# Temp.net
KiCad netlist of a schematic drawn in EAGLE
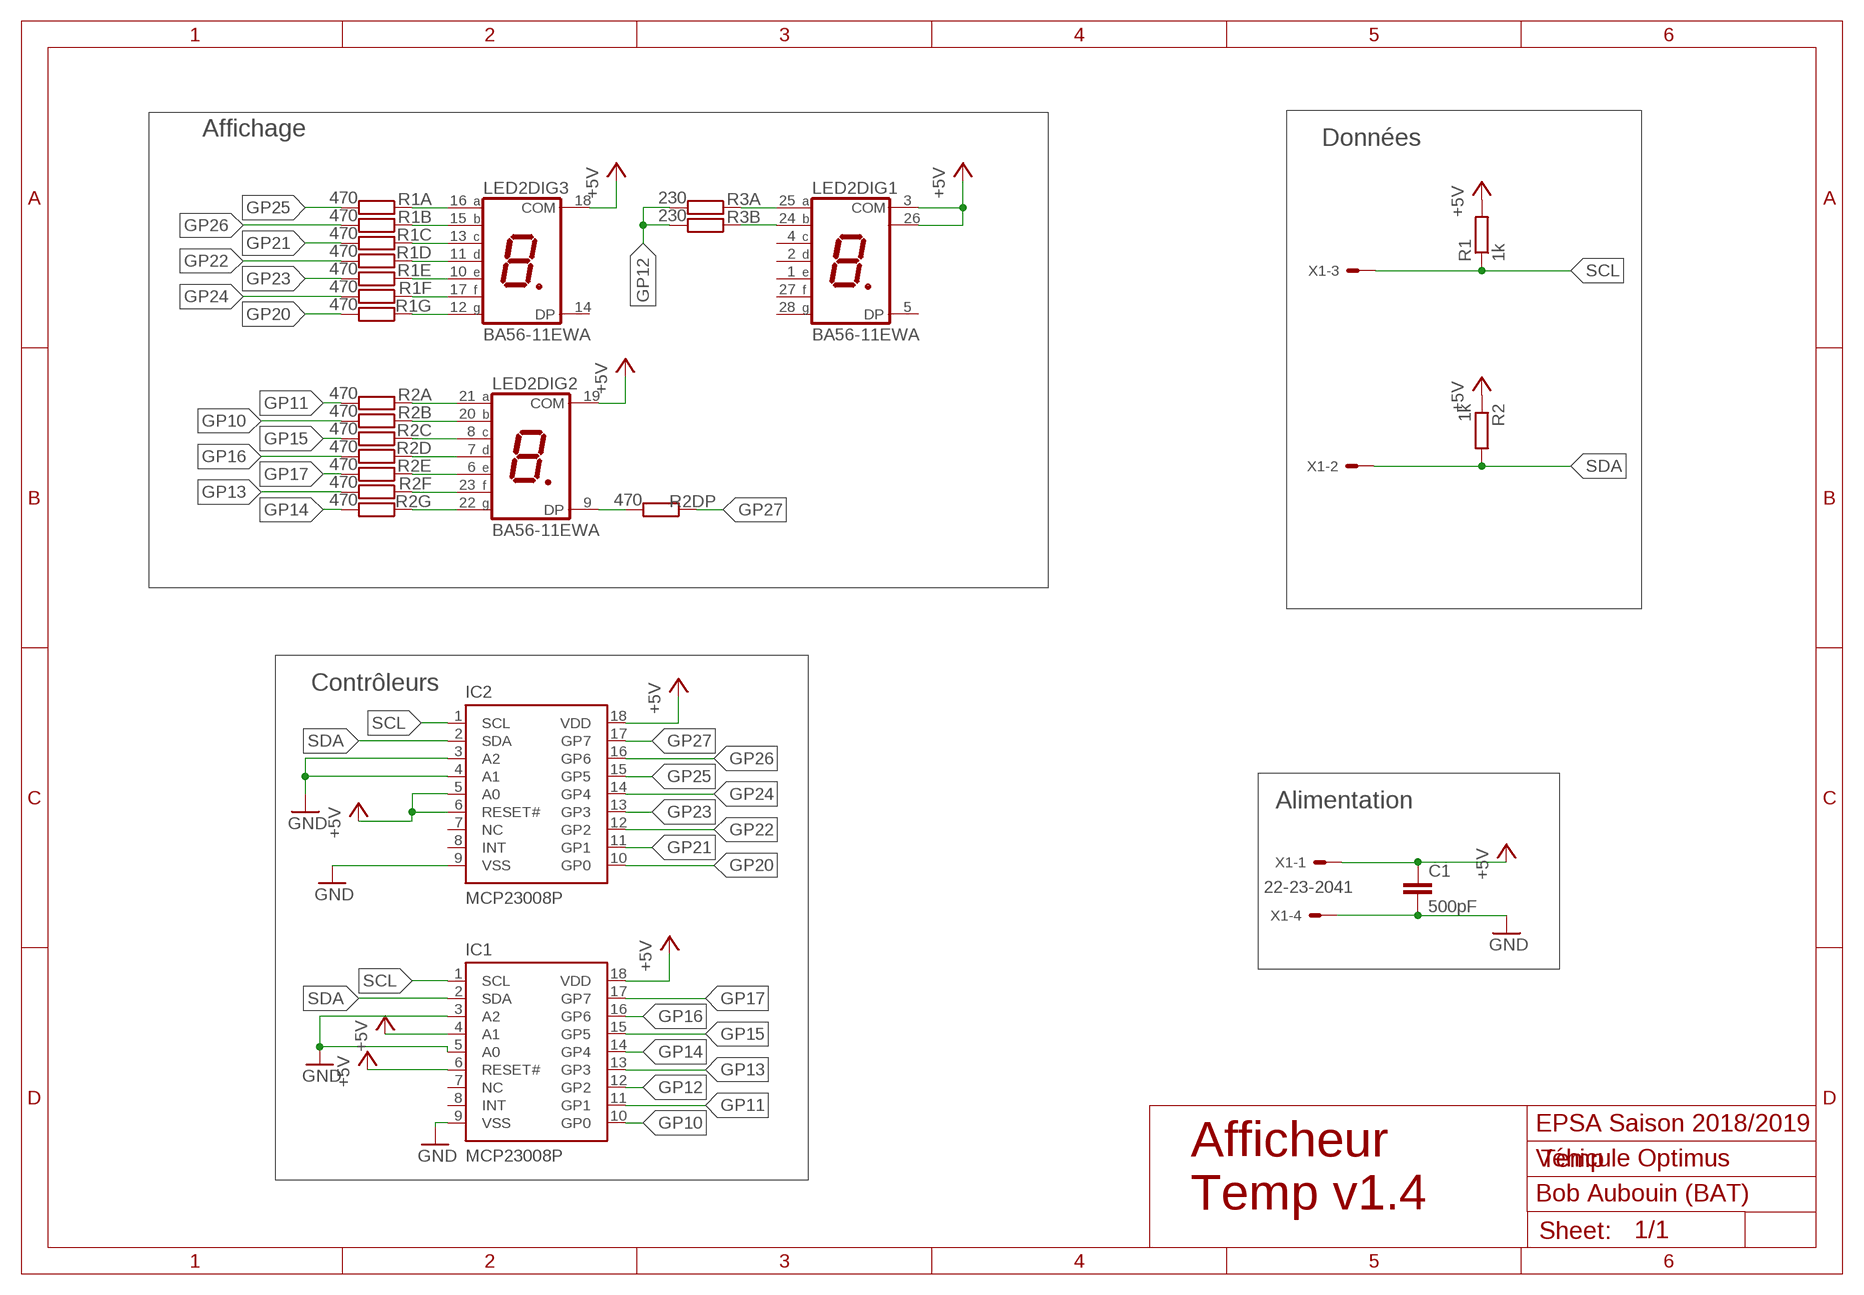
[diagram p0: schematic, sheet 1]

(export (version "E")
  (design (tool "Eeschema 10.0.6"))
  (components
    (comp (ref "C1")
      (value "500pF")
      (footprint "eagle-import:C025-025X050")
      (libsource (lib "eagle-import") (part "C-EU025-025X050"))
    )
    (comp (ref "IC1")
      (value "MCP23008P")
      (footprint "eagle-import:DIL18")
      (libsource (lib "eagle-import") (part "MCP23008P"))
    )
    (comp (ref "IC2")
      (value "MCP23008P")
      (footprint "eagle-import:DIL18")
      (libsource (lib "eagle-import") (part "MCP23008P"))
    )
    (comp (ref "LED2")
      (value "BA56-11EWA")
      (footprint "eagle-import:BA_BC56")
      (libsource (lib "eagle-import") (part "B?56-11WAAE"))
    )
    (comp (ref "R1")
      (value "1k")
      (footprint "eagle-import:0204_7")
      (libsource (lib "eagle-import") (part "R-EU_0204/7"))
    )
    (comp (ref "R1A")
      (value "470")
      (footprint "eagle-import:0204_7")
      (libsource (lib "eagle-import") (part "R-EU_0204/7"))
    )
    (comp (ref "R1B")
      (value "470")
      (footprint "eagle-import:0204_7")
      (libsource (lib "eagle-import") (part "R-EU_0204/7"))
    )
    (comp (ref "R1C")
      (value "470")
      (footprint "eagle-import:0204_7")
      (libsource (lib "eagle-import") (part "R-EU_0204/7"))
    )
    (comp (ref "R1D")
      (value "470")
      (footprint "eagle-import:0204_7")
      (libsource (lib "eagle-import") (part "R-EU_0204/7"))
    )
    (comp (ref "R1E")
      (value "470")
      (footprint "eagle-import:0204_7")
      (libsource (lib "eagle-import") (part "R-EU_0204/7"))
    )
    (comp (ref "R1F")
      (value "470")
      (footprint "eagle-import:0204_7")
      (libsource (lib "eagle-import") (part "R-EU_0204/7"))
    )
    (comp (ref "R1G")
      (value "470")
      (footprint "eagle-import:0204_7")
      (libsource (lib "eagle-import") (part "R-EU_0204/7"))
    )
    (comp (ref "R2")
      (value "1k")
      (footprint "eagle-import:0204_7")
      (libsource (lib "eagle-import") (part "R-EU_0204/7"))
    )
    (comp (ref "R2A")
      (value "470")
      (footprint "eagle-import:0204_7")
      (libsource (lib "eagle-import") (part "R-EU_0204/7"))
    )
    (comp (ref "R2B")
      (value "470")
      (footprint "eagle-import:0204_7")
      (libsource (lib "eagle-import") (part "R-EU_0204/7"))
    )
    (comp (ref "R2C")
      (value "470")
      (footprint "eagle-import:0204_7")
      (libsource (lib "eagle-import") (part "R-EU_0204/7"))
    )
    (comp (ref "R2D")
      (value "470")
      (footprint "eagle-import:0204_7")
      (libsource (lib "eagle-import") (part "R-EU_0204/7"))
    )
    (comp (ref "R2DP")
      (value "470")
      (footprint "eagle-import:0204_7")
      (libsource (lib "eagle-import") (part "R-EU_0204/7"))
    )
    (comp (ref "R2E")
      (value "470")
      (footprint "eagle-import:0204_7")
      (libsource (lib "eagle-import") (part "R-EU_0204/7"))
    )
    (comp (ref "R2F")
      (value "470")
      (footprint "eagle-import:0204_7")
      (libsource (lib "eagle-import") (part "R-EU_0204/7"))
    )
    (comp (ref "R2G")
      (value "470")
      (footprint "eagle-import:0204_7")
      (libsource (lib "eagle-import") (part "R-EU_0204/7"))
    )
    (comp (ref "R3A")
      (value "230")
      (footprint "eagle-import:0204_7")
      (libsource (lib "eagle-import") (part "R-EU_0204/7"))
    )
    (comp (ref "R3B")
      (value "230")
      (footprint "eagle-import:0204_7")
      (libsource (lib "eagle-import") (part "R-EU_0204/7"))
    )
    (comp (ref "X1")
      (value "22-23-2041")
      (footprint "eagle-import:22-23-2041")
      (fields (field (name "MF") "MOLEX"))
      (libsource (lib "eagle-import") (part "22-23-2041"))
    )
  )
  (nets
    (net (code "1") (name "+5V") (class "Default")
      (node (ref "C1") (pin "1") (pinfunction "1_1") (pintype "passive"))
      (node (ref "IC1") (pin "18") (pinfunction "VDD_18") (pintype "power_in"))
      (node (ref "IC1") (pin "4") (pinfunction "A1_4") (pintype "input"))
      (node (ref "IC1") (pin "6") (pinfunction "RESET#_6") (pintype "input"))
      (node (ref "IC2") (pin "18") (pinfunction "VDD_18") (pintype "power_in"))
      (node (ref "IC2") (pin "5") (pinfunction "A0_5") (pintype "input"))
      (node (ref "IC2") (pin "6") (pinfunction "RESET#_6") (pintype "input"))
      (node (ref "LED2") (pin "18") (pinfunction "COM_18") (pintype "passive"))
      (node (ref "LED2") (pin "19") (pinfunction "COM_19") (pintype "passive"))
      (node (ref "LED2") (pin "26") (pinfunction "COM_26") (pintype "passive"))
      (node (ref "LED2") (pin "3") (pinfunction "COM_3") (pintype "passive"))
      (node (ref "R1") (pin "2") (pinfunction "2_2") (pintype "passive"))
      (node (ref "R2") (pin "1") (pinfunction "1_1") (pintype "passive"))
      (node (ref "X1") (pin "1") (pinfunction "S_1") (pintype "passive"))
    )
    (net (code "2") (name "GND") (class "Default")
      (node (ref "C1") (pin "2") (pinfunction "2_2") (pintype "passive"))
      (node (ref "IC1") (pin "3") (pinfunction "A2_3") (pintype "input"))
      (node (ref "IC1") (pin "5") (pinfunction "A0_5") (pintype "input"))
      (node (ref "IC1") (pin "9") (pinfunction "VSS_9") (pintype "power_in"))
      (node (ref "IC2") (pin "3") (pinfunction "A2_3") (pintype "input"))
      (node (ref "IC2") (pin "4") (pinfunction "A1_4") (pintype "input"))
      (node (ref "IC2") (pin "9") (pinfunction "VSS_9") (pintype "power_in"))
      (node (ref "X1") (pin "4") (pinfunction "S_4") (pintype "passive"))
    )
    (net (code "3") (name "GP10") (class "Default")
      (node (ref "IC1") (pin "10") (pinfunction "GP0_10") (pintype "bidirectional"))
      (node (ref "R2B") (pin "2") (pinfunction "2_2") (pintype "passive"))
    )
    (net (code "4") (name "GP11") (class "Default")
      (node (ref "IC1") (pin "11") (pinfunction "GP1_11") (pintype "bidirectional"))
      (node (ref "R2A") (pin "2") (pinfunction "2_2") (pintype "passive"))
    )
    (net (code "5") (name "GP12") (class "Default")
      (node (ref "IC1") (pin "12") (pinfunction "GP2_12") (pintype "bidirectional"))
      (node (ref "R3A") (pin "2") (pinfunction "2_2") (pintype "passive"))
      (node (ref "R3B") (pin "2") (pinfunction "2_2") (pintype "passive"))
    )
    (net (code "6") (name "GP13") (class "Default")
      (node (ref "IC1") (pin "13") (pinfunction "GP3_13") (pintype "bidirectional"))
      (node (ref "R2F") (pin "2") (pinfunction "2_2") (pintype "passive"))
    )
    (net (code "7") (name "GP14") (class "Default")
      (node (ref "IC1") (pin "14") (pinfunction "GP4_14") (pintype "bidirectional"))
      (node (ref "R2G") (pin "2") (pinfunction "2_2") (pintype "passive"))
    )
    (net (code "8") (name "GP15") (class "Default")
      (node (ref "IC1") (pin "15") (pinfunction "GP5_15") (pintype "bidirectional"))
      (node (ref "R2C") (pin "2") (pinfunction "2_2") (pintype "passive"))
    )
    (net (code "9") (name "GP16") (class "Default")
      (node (ref "IC1") (pin "16") (pinfunction "GP6_16") (pintype "bidirectional"))
      (node (ref "R2D") (pin "2") (pinfunction "2_2") (pintype "passive"))
    )
    (net (code "10") (name "GP17") (class "Default")
      (node (ref "IC1") (pin "17") (pinfunction "GP7_17") (pintype "bidirectional"))
      (node (ref "R2E") (pin "2") (pinfunction "2_2") (pintype "passive"))
    )
    (net (code "11") (name "GP20") (class "Default")
      (node (ref "IC2") (pin "10") (pinfunction "GP0_10") (pintype "bidirectional"))
      (node (ref "R1G") (pin "2") (pinfunction "2_2") (pintype "passive"))
    )
    (net (code "12") (name "GP21") (class "Default")
      (node (ref "IC2") (pin "11") (pinfunction "GP1_11") (pintype "bidirectional"))
      (node (ref "R1C") (pin "2") (pinfunction "2_2") (pintype "passive"))
    )
    (net (code "13") (name "GP22") (class "Default")
      (node (ref "IC2") (pin "12") (pinfunction "GP2_12") (pintype "bidirectional"))
      (node (ref "R1D") (pin "2") (pinfunction "2_2") (pintype "passive"))
    )
    (net (code "14") (name "GP23") (class "Default")
      (node (ref "IC2") (pin "13") (pinfunction "GP3_13") (pintype "bidirectional"))
      (node (ref "R1E") (pin "2") (pinfunction "2_2") (pintype "passive"))
    )
    (net (code "15") (name "GP24") (class "Default")
      (node (ref "IC2") (pin "14") (pinfunction "GP4_14") (pintype "bidirectional"))
      (node (ref "R1F") (pin "2") (pinfunction "2_2") (pintype "passive"))
    )
    (net (code "16") (name "GP25") (class "Default")
      (node (ref "IC2") (pin "15") (pinfunction "GP5_15") (pintype "bidirectional"))
      (node (ref "R1A") (pin "2") (pinfunction "2_2") (pintype "passive"))
    )
    (net (code "17") (name "GP26") (class "Default")
      (node (ref "IC2") (pin "16") (pinfunction "GP6_16") (pintype "bidirectional"))
      (node (ref "R1B") (pin "2") (pinfunction "2_2") (pintype "passive"))
    )
    (net (code "18") (name "GP27") (class "Default")
      (node (ref "IC2") (pin "17") (pinfunction "GP7_17") (pintype "bidirectional"))
      (node (ref "R2DP") (pin "1") (pinfunction "1_1") (pintype "passive"))
    )
    (net (code "19") (name "Net-(LED2A-A)") (class "Default")
      (node (ref "LED2") (pin "25") (pinfunction "A_25") (pintype "passive"))
      (node (ref "R3A") (pin "1") (pinfunction "1_1") (pintype "passive"))
    )
    (net (code "20") (name "Net-(LED2A-B)") (class "Default")
      (node (ref "LED2") (pin "24") (pinfunction "B_24") (pintype "passive"))
      (node (ref "R3B") (pin "1") (pinfunction "1_1") (pintype "passive"))
    )
    (net (code "21") (name "Net-(LED2B-A)") (class "Default")
      (node (ref "LED2") (pin "21") (pinfunction "A_21") (pintype "passive"))
      (node (ref "R2A") (pin "1") (pinfunction "1_1") (pintype "passive"))
    )
    (net (code "22") (name "Net-(LED2B-B)") (class "Default")
      (node (ref "LED2") (pin "20") (pinfunction "B_20") (pintype "passive"))
      (node (ref "R2B") (pin "1") (pinfunction "1_1") (pintype "passive"))
    )
    (net (code "23") (name "Net-(LED2B-C)") (class "Default")
      (node (ref "LED2") (pin "8") (pinfunction "C_8") (pintype "passive"))
      (node (ref "R2C") (pin "1") (pinfunction "1_1") (pintype "passive"))
    )
    (net (code "24") (name "Net-(LED2B-D)") (class "Default")
      (node (ref "LED2") (pin "7") (pinfunction "D_7") (pintype "passive"))
      (node (ref "R2D") (pin "1") (pinfunction "1_1") (pintype "passive"))
    )
    (net (code "25") (name "Net-(LED2B-DP)") (class "Default")
      (node (ref "LED2") (pin "9") (pinfunction "DP_9") (pintype "passive"))
      (node (ref "R2DP") (pin "2") (pinfunction "2_2") (pintype "passive"))
    )
    (net (code "26") (name "Net-(LED2B-E)") (class "Default")
      (node (ref "LED2") (pin "6") (pinfunction "E_6") (pintype "passive"))
      (node (ref "R2E") (pin "1") (pinfunction "1_1") (pintype "passive"))
    )
    (net (code "27") (name "Net-(LED2B-F)") (class "Default")
      (node (ref "LED2") (pin "23") (pinfunction "F_23") (pintype "passive"))
      (node (ref "R2F") (pin "1") (pinfunction "1_1") (pintype "passive"))
    )
    (net (code "28") (name "Net-(LED2B-G)") (class "Default")
      (node (ref "LED2") (pin "22") (pinfunction "G_22") (pintype "passive"))
      (node (ref "R2G") (pin "1") (pinfunction "1_1") (pintype "passive"))
    )
    (net (code "29") (name "Net-(LED2C-A)") (class "Default")
      (node (ref "LED2") (pin "16") (pinfunction "A_16") (pintype "passive"))
      (node (ref "R1A") (pin "1") (pinfunction "1_1") (pintype "passive"))
    )
    (net (code "30") (name "Net-(LED2C-B)") (class "Default")
      (node (ref "LED2") (pin "15") (pinfunction "B_15") (pintype "passive"))
      (node (ref "R1B") (pin "1") (pinfunction "1_1") (pintype "passive"))
    )
    (net (code "31") (name "Net-(LED2C-C)") (class "Default")
      (node (ref "LED2") (pin "13") (pinfunction "C_13") (pintype "passive"))
      (node (ref "R1C") (pin "1") (pinfunction "1_1") (pintype "passive"))
    )
    (net (code "32") (name "Net-(LED2C-D)") (class "Default")
      (node (ref "LED2") (pin "11") (pinfunction "D_11") (pintype "passive"))
      (node (ref "R1D") (pin "1") (pinfunction "1_1") (pintype "passive"))
    )
    (net (code "33") (name "Net-(LED2C-E)") (class "Default")
      (node (ref "LED2") (pin "10") (pinfunction "E_10") (pintype "passive"))
      (node (ref "R1E") (pin "1") (pinfunction "1_1") (pintype "passive"))
    )
    (net (code "34") (name "Net-(LED2C-F)") (class "Default")
      (node (ref "LED2") (pin "17") (pinfunction "F_17") (pintype "passive"))
      (node (ref "R1F") (pin "1") (pinfunction "1_1") (pintype "passive"))
    )
    (net (code "35") (name "Net-(LED2C-G)") (class "Default")
      (node (ref "LED2") (pin "12") (pinfunction "G_12") (pintype "passive"))
      (node (ref "R1G") (pin "1") (pinfunction "1_1") (pintype "passive"))
    )
    (net (code "36") (name "SCL") (class "Default")
      (node (ref "IC1") (pin "1") (pinfunction "SCL_1") (pintype "input"))
      (node (ref "IC2") (pin "1") (pinfunction "SCL_1") (pintype "input"))
      (node (ref "R1") (pin "1") (pinfunction "1_1") (pintype "passive"))
      (node (ref "X1") (pin "3") (pinfunction "S_3") (pintype "passive"))
    )
    (net (code "37") (name "SDA") (class "Default")
      (node (ref "IC1") (pin "2") (pinfunction "SDA_2") (pintype "bidirectional"))
      (node (ref "IC2") (pin "2") (pinfunction "SDA_2") (pintype "bidirectional"))
      (node (ref "R2") (pin "2") (pinfunction "2_2") (pintype "passive"))
      (node (ref "X1") (pin "2") (pinfunction "S_2") (pintype "passive"))
    )
    (net (code "38") (name "unconnected-(IC1-INT-Pad8)") (class "Default")
      (node (ref "IC1") (pin "8") (pinfunction "INT_8") (pintype "output"))
    )
    (net (code "39") (name "unconnected-(IC1-NC-Pad7)") (class "Default")
      (node (ref "IC1") (pin "7") (pinfunction "NC_7") (pintype "no_connect"))
    )
    (net (code "40") (name "unconnected-(IC2-INT-Pad8)") (class "Default")
      (node (ref "IC2") (pin "8") (pinfunction "INT_8") (pintype "output"))
    )
    (net (code "41") (name "unconnected-(IC2-NC-Pad7)") (class "Default")
      (node (ref "IC2") (pin "7") (pinfunction "NC_7") (pintype "no_connect"))
    )
    (net (code "42") (name "unconnected-(LED2A-C-Pad4)") (class "Default")
      (node (ref "LED2") (pin "4") (pinfunction "C_4") (pintype "passive"))
    )
    (net (code "43") (name "unconnected-(LED2A-D-Pad2)") (class "Default")
      (node (ref "LED2") (pin "2") (pinfunction "D_2") (pintype "passive"))
    )
    (net (code "44") (name "unconnected-(LED2A-DP-Pad5)") (class "Default")
      (node (ref "LED2") (pin "5") (pinfunction "DP_5") (pintype "passive"))
    )
    (net (code "45") (name "unconnected-(LED2A-E-Pad1)") (class "Default")
      (node (ref "LED2") (pin "1") (pinfunction "E_1") (pintype "passive"))
    )
    (net (code "46") (name "unconnected-(LED2A-F-Pad27)") (class "Default")
      (node (ref "LED2") (pin "27") (pinfunction "F_27") (pintype "passive"))
    )
    (net (code "47") (name "unconnected-(LED2A-G-Pad28)") (class "Default")
      (node (ref "LED2") (pin "28") (pinfunction "G_28") (pintype "passive"))
    )
    (net (code "48") (name "unconnected-(LED2C-DP-Pad14)") (class "Default")
      (node (ref "LED2") (pin "14") (pinfunction "DP_14") (pintype "passive"))
    )
  )
)
